# ECU_AutoRC_MOT_DRIVER_r00.net
KiCad netlist of a schematic drawn in Altium Designer
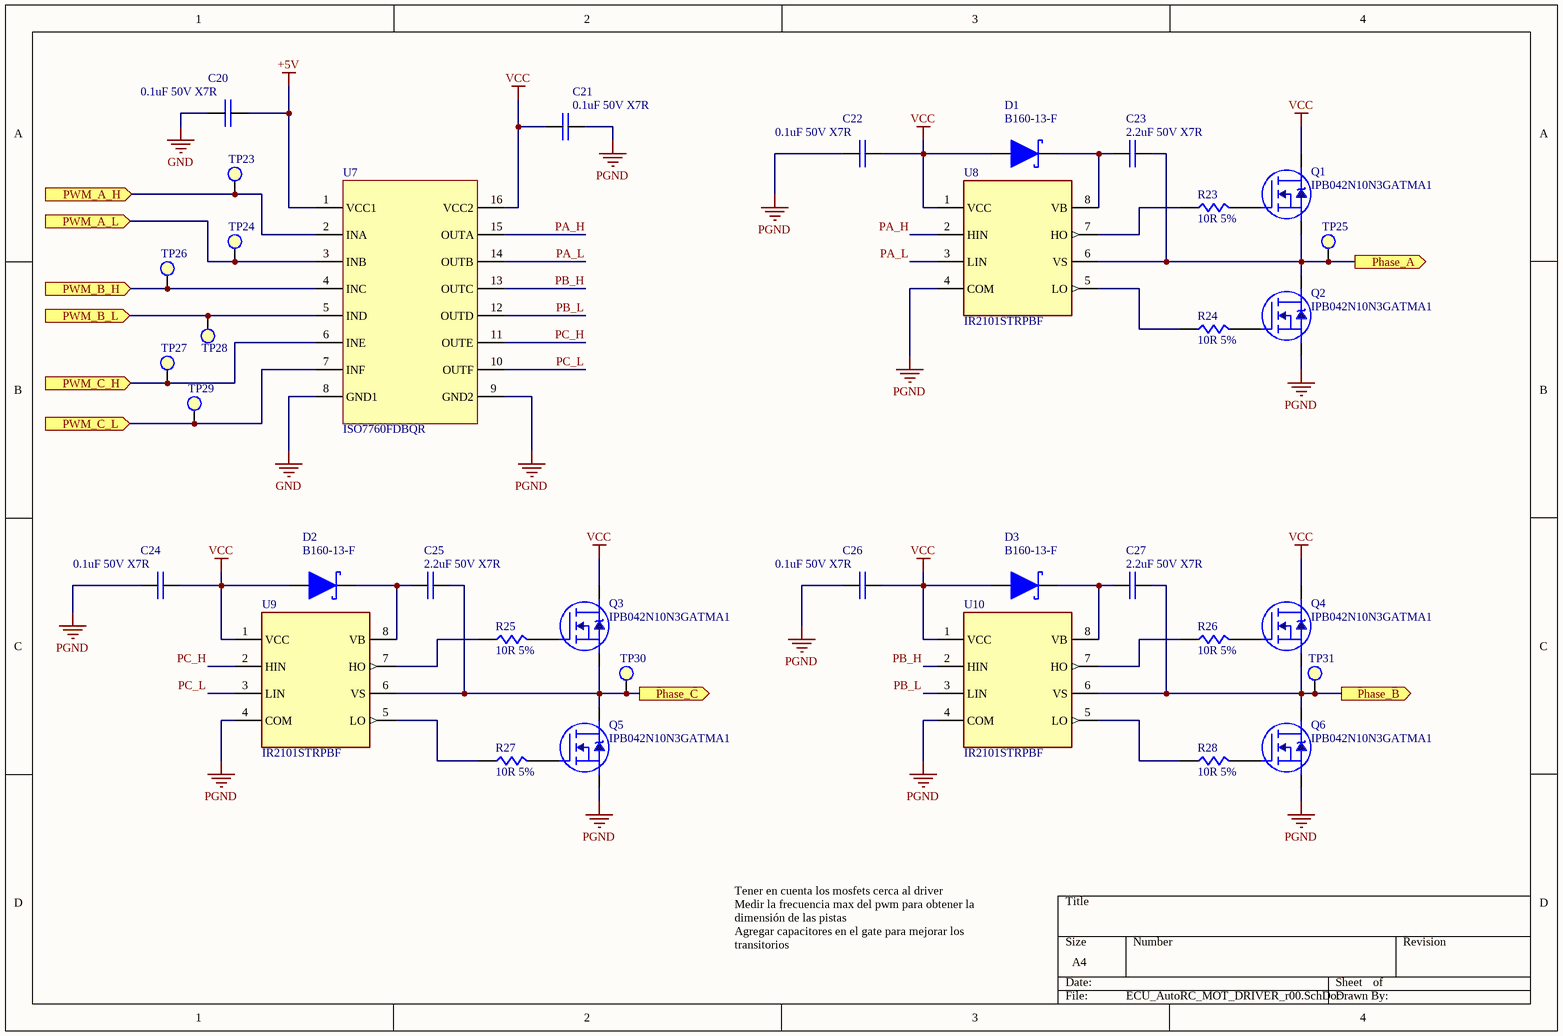
[diagram p0: ECU_AutoRC_MOT_DRIVER_r00.SchDoc]

(export (version "E")
  (design (tool "Eeschema 10.0.6"))
  (components
    (comp (ref "C20")
      (value "0.1uF 50V X7R")
      (footprint "C_0805")
      (description "Non Polarizated Capacitor")
      (libsource (lib "ECU_AutoRC_r00") (part "Capacitor NP"))
    )
    (comp (ref "C21")
      (value "0.1uF 50V X7R")
      (footprint "C_0805")
      (description "Non Polarizated Capacitor")
      (libsource (lib "ECU_AutoRC_r00") (part "Capacitor NP"))
    )
    (comp (ref "C22")
      (value "0.1uF 50V X7R")
      (footprint "C_0805")
      (description "Non Polarizated Capacitor")
      (libsource (lib "ECU_AutoRC_r00") (part "Capacitor NP"))
    )
    (comp (ref "C23")
      (value "2.2uF 50V X7R")
      (footprint "C_0805")
      (description "Non Polarizated Capacitor")
      (libsource (lib "ECU_AutoRC_r00") (part "Capacitor NP"))
    )
    (comp (ref "C24")
      (value "0.1uF 50V X7R")
      (footprint "C_0805")
      (description "Non Polarizated Capacitor")
      (libsource (lib "ECU_AutoRC_r00") (part "Capacitor NP"))
    )
    (comp (ref "C25")
      (value "2.2uF 50V X7R")
      (footprint "C_0805")
      (description "Non Polarizated Capacitor")
      (libsource (lib "ECU_AutoRC_r00") (part "Capacitor NP"))
    )
    (comp (ref "C26")
      (value "0.1uF 50V X7R")
      (footprint "C_0805")
      (description "Non Polarizated Capacitor")
      (libsource (lib "ECU_AutoRC_r00") (part "Capacitor NP"))
    )
    (comp (ref "C27")
      (value "2.2uF 50V X7R")
      (footprint "C_0805")
      (description "Non Polarizated Capacitor")
      (libsource (lib "ECU_AutoRC_r00") (part "Capacitor NP"))
    )
    (comp (ref "D1")
      (value "B160-13-F")
      (footprint "D_SMA")
      (description "Diode Schottky")
      (libsource (lib "ECU_AutoRC_r00") (part "Diode_Schottky"))
    )
    (comp (ref "D2")
      (value "B160-13-F")
      (footprint "D_SMA")
      (description "Diode Schottky")
      (libsource (lib "ECU_AutoRC_r00") (part "Diode_Schottky"))
    )
    (comp (ref "D3")
      (value "B160-13-F")
      (footprint "D_SMA")
      (description "Diode Schottky")
      (libsource (lib "ECU_AutoRC_r00") (part "Diode_Schottky"))
    )
    (comp (ref "Q1")
      (value "IPB042N10N3GATMA1")
      (footprint "TO263-3")
      (description "Mosfet N")
      (libsource (lib "ECU_AutoRC_r00") (part "NMOS"))
    )
    (comp (ref "Q2")
      (value "IPB042N10N3GATMA1")
      (footprint "TO263-3")
      (description "Mosfet N")
      (libsource (lib "ECU_AutoRC_r00") (part "NMOS"))
    )
    (comp (ref "Q3")
      (value "IPB042N10N3GATMA1")
      (footprint "TO263-3")
      (description "Mosfet N")
      (libsource (lib "ECU_AutoRC_r00") (part "NMOS"))
    )
    (comp (ref "Q4")
      (value "IPB042N10N3GATMA1")
      (footprint "TO263-3")
      (description "Mosfet N")
      (libsource (lib "ECU_AutoRC_r00") (part "NMOS"))
    )
    (comp (ref "Q5")
      (value "IPB042N10N3GATMA1")
      (footprint "TO263-3")
      (description "Mosfet N")
      (libsource (lib "ECU_AutoRC_r00") (part "NMOS"))
    )
    (comp (ref "Q6")
      (value "IPB042N10N3GATMA1")
      (footprint "TO263-3")
      (description "Mosfet N")
      (libsource (lib "ECU_AutoRC_r00") (part "NMOS"))
    )
    (comp (ref "R23")
      (value "10R 5%")
      (footprint "R_0805")
      (description "Resistor")
      (libsource (lib "ECU_AutoRC_r00") (part "Resistor"))
    )
    (comp (ref "R24")
      (value "10R 5%")
      (footprint "R_0805")
      (description "Resistor")
      (libsource (lib "ECU_AutoRC_r00") (part "Resistor"))
    )
    (comp (ref "R25")
      (value "10R 5%")
      (footprint "R_0805")
      (description "Resistor")
      (libsource (lib "ECU_AutoRC_r00") (part "Resistor"))
    )
    (comp (ref "R26")
      (value "10R 5%")
      (footprint "R_0805")
      (description "Resistor")
      (libsource (lib "ECU_AutoRC_r00") (part "Resistor"))
    )
    (comp (ref "R27")
      (value "10R 5%")
      (footprint "R_0805")
      (description "Resistor")
      (libsource (lib "ECU_AutoRC_r00") (part "Resistor"))
    )
    (comp (ref "R28")
      (value "10R 5%")
      (footprint "R_0805")
      (description "Resistor")
      (libsource (lib "ECU_AutoRC_r00") (part "Resistor"))
    )
    (comp (ref "TP23")
      (value "Test Point")
      (footprint "TEST_POINT")
      (libsource (lib "ECU_AutoRC_r00") (part "TestPoint"))
    )
    (comp (ref "TP24")
      (value "Test Point")
      (footprint "TEST_POINT")
      (libsource (lib "ECU_AutoRC_r00") (part "TestPoint"))
    )
    (comp (ref "TP25")
      (value "Test Point")
      (footprint "TEST_POINT")
      (libsource (lib "ECU_AutoRC_r00") (part "TestPoint"))
    )
    (comp (ref "TP26")
      (value "Test Point")
      (footprint "TEST_POINT")
      (libsource (lib "ECU_AutoRC_r00") (part "TestPoint"))
    )
    (comp (ref "TP27")
      (value "Test Point")
      (footprint "TEST_POINT")
      (libsource (lib "ECU_AutoRC_r00") (part "TestPoint"))
    )
    (comp (ref "TP28")
      (value "Test Point")
      (footprint "TEST_POINT")
      (libsource (lib "ECU_AutoRC_r00") (part "TestPoint"))
    )
    (comp (ref "TP29")
      (value "Test Point")
      (footprint "TEST_POINT")
      (libsource (lib "ECU_AutoRC_r00") (part "TestPoint"))
    )
    (comp (ref "TP30")
      (value "Test Point")
      (footprint "TEST_POINT")
      (libsource (lib "ECU_AutoRC_r00") (part "TestPoint"))
    )
    (comp (ref "TP31")
      (value "Test Point")
      (footprint "TEST_POINT")
      (libsource (lib "ECU_AutoRC_r00") (part "TestPoint"))
    )
    (comp (ref "U7")
      (value "ISO7760FDBQR")
      (footprint "IC_SSOP16")
      (description "DGTL ISOLTR 3KV 6CH GP 16-SSOP")
      (libsource (lib "ECU_AutoRC_r00") (part "ISO7760FDBQR"))
    )
    (comp (ref "U8")
      (value "IR2101STRPBF")
      (footprint "IC_8SOIC")
      (description "Half-Bridge Gate Driver IC Non-Inverting 8-SOIC")
      (libsource (lib "ECU_AutoRC_r00") (part "IR2101STRPBF"))
    )
    (comp (ref "U9")
      (value "IR2101STRPBF")
      (footprint "IC_8SOIC")
      (description "Half-Bridge Gate Driver IC Non-Inverting 8-SOIC")
      (libsource (lib "ECU_AutoRC_r00") (part "IR2101STRPBF"))
    )
    (comp (ref "U10")
      (value "IR2101STRPBF")
      (footprint "IC_8SOIC")
      (description "Half-Bridge Gate Driver IC Non-Inverting 8-SOIC")
      (libsource (lib "ECU_AutoRC_r00") (part "IR2101STRPBF"))
    )
  )
  (nets
    (net (code "1") (name "+5V") (class "Default")
      (node (ref "C20") (pin "2") (pinfunction "2_2") (pintype "passive"))
      (node (ref "U7") (pin "1") (pinfunction "VCC1_1") (pintype "passive"))
    )
    (net (code "2") (name "/PA_H") (class "Default")
      (node (ref "U7") (pin "15") (pinfunction "OUTA_15") (pintype "passive"))
      (node (ref "U8") (pin "2") (pinfunction "HIN_2") (pintype "passive"))
    )
    (net (code "3") (name "/PA_L") (class "Default")
      (node (ref "U7") (pin "14") (pinfunction "OUTB_14") (pintype "passive"))
      (node (ref "U8") (pin "3") (pinfunction "LIN_3") (pintype "passive"))
    )
    (net (code "4") (name "/PB_H") (class "Default")
      (node (ref "U10") (pin "2") (pinfunction "HIN_2") (pintype "passive"))
      (node (ref "U7") (pin "13") (pinfunction "OUTC_13") (pintype "passive"))
    )
    (net (code "5") (name "/PB_L") (class "Default")
      (node (ref "U10") (pin "3") (pinfunction "LIN_3") (pintype "passive"))
      (node (ref "U7") (pin "12") (pinfunction "OUTD_12") (pintype "passive"))
    )
    (net (code "6") (name "/PC_H") (class "Default")
      (node (ref "U7") (pin "11") (pinfunction "OUTE_11") (pintype "passive"))
      (node (ref "U9") (pin "2") (pinfunction "HIN_2") (pintype "passive"))
    )
    (net (code "7") (name "/PC_L") (class "Default")
      (node (ref "U7") (pin "10") (pinfunction "OUTF_10") (pintype "passive"))
      (node (ref "U9") (pin "3") (pinfunction "LIN_3") (pintype "passive"))
    )
    (net (code "8") (name "/PWM_A_H") (class "Default")
      (node (ref "TP23") (pin "1") (pintype "passive"))
      (node (ref "U7") (pin "2") (pinfunction "INA_2") (pintype "passive"))
    )
    (net (code "9") (name "/PWM_A_L") (class "Default")
      (node (ref "TP24") (pin "1") (pintype "passive"))
      (node (ref "U7") (pin "3") (pinfunction "INB_3") (pintype "passive"))
    )
    (net (code "10") (name "/PWM_B_H") (class "Default")
      (node (ref "TP26") (pin "1") (pintype "passive"))
      (node (ref "U7") (pin "4") (pinfunction "INC_4") (pintype "passive"))
    )
    (net (code "11") (name "/PWM_B_L") (class "Default")
      (node (ref "TP28") (pin "1") (pintype "passive"))
      (node (ref "U7") (pin "5") (pinfunction "IND_5") (pintype "passive"))
    )
    (net (code "12") (name "/PWM_C_H") (class "Default")
      (node (ref "TP27") (pin "1") (pintype "passive"))
      (node (ref "U7") (pin "6") (pinfunction "INE_6") (pintype "passive"))
    )
    (net (code "13") (name "/PWM_C_L") (class "Default")
      (node (ref "TP29") (pin "1") (pintype "passive"))
      (node (ref "U7") (pin "7") (pinfunction "INF_7") (pintype "passive"))
    )
    (net (code "14") (name "/Phase_A") (class "Default")
      (node (ref "C23") (pin "2") (pinfunction "2_2") (pintype "passive"))
      (node (ref "Q1") (pin "3") (pinfunction "SOURCE_3") (pintype "passive"))
      (node (ref "Q2") (pin "2") (pinfunction "DRAIN_2") (pintype "passive"))
      (node (ref "TP25") (pin "1") (pintype "passive"))
      (node (ref "U8") (pin "6") (pinfunction "VS_6") (pintype "passive"))
    )
    (net (code "15") (name "/Phase_B") (class "Default")
      (node (ref "C27") (pin "2") (pinfunction "2_2") (pintype "passive"))
      (node (ref "Q4") (pin "3") (pinfunction "SOURCE_3") (pintype "passive"))
      (node (ref "Q6") (pin "2") (pinfunction "DRAIN_2") (pintype "passive"))
      (node (ref "TP31") (pin "1") (pintype "passive"))
      (node (ref "U10") (pin "6") (pinfunction "VS_6") (pintype "passive"))
    )
    (net (code "16") (name "/Phase_C") (class "Default")
      (node (ref "C25") (pin "2") (pinfunction "2_2") (pintype "passive"))
      (node (ref "Q3") (pin "3") (pinfunction "SOURCE_3") (pintype "passive"))
      (node (ref "Q5") (pin "2") (pinfunction "DRAIN_2") (pintype "passive"))
      (node (ref "TP30") (pin "1") (pintype "passive"))
      (node (ref "U9") (pin "6") (pinfunction "VS_6") (pintype "passive"))
    )
    (net (code "17") (name "GND") (class "Default")
      (node (ref "C20") (pin "1") (pinfunction "1_1") (pintype "passive"))
      (node (ref "U7") (pin "8") (pinfunction "GND1_8") (pintype "passive"))
    )
    (net (code "18") (name "Net-(D1-Catode)") (class "Default")
      (node (ref "C23") (pin "1") (pinfunction "1_1") (pintype "passive"))
      (node (ref "D1") (pin "2") (pinfunction "Catode_2") (pintype "passive"))
      (node (ref "U8") (pin "8") (pinfunction "VB_8") (pintype "passive"))
    )
    (net (code "19") (name "Net-(D2-Catode)") (class "Default")
      (node (ref "C25") (pin "1") (pinfunction "1_1") (pintype "passive"))
      (node (ref "D2") (pin "2") (pinfunction "Catode_2") (pintype "passive"))
      (node (ref "U9") (pin "8") (pinfunction "VB_8") (pintype "passive"))
    )
    (net (code "20") (name "Net-(D3-Catode)") (class "Default")
      (node (ref "C27") (pin "1") (pinfunction "1_1") (pintype "passive"))
      (node (ref "D3") (pin "2") (pinfunction "Catode_2") (pintype "passive"))
      (node (ref "U10") (pin "8") (pinfunction "VB_8") (pintype "passive"))
    )
    (net (code "21") (name "Net-(Q1-GATE)") (class "Default")
      (node (ref "Q1") (pin "1") (pinfunction "GATE_1") (pintype "passive"))
      (node (ref "R23") (pin "2") (pinfunction "2_2") (pintype "passive"))
    )
    (net (code "22") (name "Net-(Q2-GATE)") (class "Default")
      (node (ref "Q2") (pin "1") (pinfunction "GATE_1") (pintype "passive"))
      (node (ref "R24") (pin "2") (pinfunction "2_2") (pintype "passive"))
    )
    (net (code "23") (name "Net-(Q3-GATE)") (class "Default")
      (node (ref "Q3") (pin "1") (pinfunction "GATE_1") (pintype "passive"))
      (node (ref "R25") (pin "2") (pinfunction "2_2") (pintype "passive"))
    )
    (net (code "24") (name "Net-(Q4-GATE)") (class "Default")
      (node (ref "Q4") (pin "1") (pinfunction "GATE_1") (pintype "passive"))
      (node (ref "R26") (pin "2") (pinfunction "2_2") (pintype "passive"))
    )
    (net (code "25") (name "Net-(Q5-GATE)") (class "Default")
      (node (ref "Q5") (pin "1") (pinfunction "GATE_1") (pintype "passive"))
      (node (ref "R27") (pin "2") (pinfunction "2_2") (pintype "passive"))
    )
    (net (code "26") (name "Net-(Q6-GATE)") (class "Default")
      (node (ref "Q6") (pin "1") (pinfunction "GATE_1") (pintype "passive"))
      (node (ref "R28") (pin "2") (pinfunction "2_2") (pintype "passive"))
    )
    (net (code "27") (name "Net-(U8-HO)") (class "Default")
      (node (ref "R23") (pin "1") (pinfunction "1_1") (pintype "passive"))
      (node (ref "U8") (pin "7") (pinfunction "HO_7") (pintype "output"))
    )
    (net (code "28") (name "Net-(U8-LO)") (class "Default")
      (node (ref "R24") (pin "1") (pinfunction "1_1") (pintype "passive"))
      (node (ref "U8") (pin "5") (pinfunction "LO_5") (pintype "output"))
    )
    (net (code "29") (name "Net-(U9-HO)") (class "Default")
      (node (ref "R25") (pin "1") (pinfunction "1_1") (pintype "passive"))
      (node (ref "U9") (pin "7") (pinfunction "HO_7") (pintype "output"))
    )
    (net (code "30") (name "Net-(U9-LO)") (class "Default")
      (node (ref "R27") (pin "1") (pinfunction "1_1") (pintype "passive"))
      (node (ref "U9") (pin "5") (pinfunction "LO_5") (pintype "output"))
    )
    (net (code "31") (name "Net-(U10-HO)") (class "Default")
      (node (ref "R26") (pin "1") (pinfunction "1_1") (pintype "passive"))
      (node (ref "U10") (pin "7") (pinfunction "HO_7") (pintype "output"))
    )
    (net (code "32") (name "Net-(U10-LO)") (class "Default")
      (node (ref "R28") (pin "1") (pinfunction "1_1") (pintype "passive"))
      (node (ref "U10") (pin "5") (pinfunction "LO_5") (pintype "output"))
    )
    (net (code "33") (name "PGND") (class "Default")
      (node (ref "C21") (pin "1") (pinfunction "1_1") (pintype "passive"))
      (node (ref "C22") (pin "1") (pinfunction "1_1") (pintype "passive"))
      (node (ref "C24") (pin "1") (pinfunction "1_1") (pintype "passive"))
      (node (ref "C26") (pin "1") (pinfunction "1_1") (pintype "passive"))
      (node (ref "Q2") (pin "3") (pinfunction "SOURCE_3") (pintype "passive"))
      (node (ref "Q5") (pin "3") (pinfunction "SOURCE_3") (pintype "passive"))
      (node (ref "Q6") (pin "3") (pinfunction "SOURCE_3") (pintype "passive"))
      (node (ref "U10") (pin "4") (pinfunction "COM_4") (pintype "passive"))
      (node (ref "U7") (pin "9") (pinfunction "GND2_9") (pintype "passive"))
      (node (ref "U8") (pin "4") (pinfunction "COM_4") (pintype "passive"))
      (node (ref "U9") (pin "4") (pinfunction "COM_4") (pintype "passive"))
    )
    (net (code "34") (name "VCC") (class "Default")
      (node (ref "C21") (pin "2") (pinfunction "2_2") (pintype "passive"))
      (node (ref "C22") (pin "2") (pinfunction "2_2") (pintype "passive"))
      (node (ref "C24") (pin "2") (pinfunction "2_2") (pintype "passive"))
      (node (ref "C26") (pin "2") (pinfunction "2_2") (pintype "passive"))
      (node (ref "D1") (pin "1") (pinfunction "Anode_1") (pintype "passive"))
      (node (ref "D2") (pin "1") (pinfunction "Anode_1") (pintype "passive"))
      (node (ref "D3") (pin "1") (pinfunction "Anode_1") (pintype "passive"))
      (node (ref "Q1") (pin "2") (pinfunction "DRAIN_2") (pintype "passive"))
      (node (ref "Q3") (pin "2") (pinfunction "DRAIN_2") (pintype "passive"))
      (node (ref "Q4") (pin "2") (pinfunction "DRAIN_2") (pintype "passive"))
      (node (ref "U10") (pin "1") (pinfunction "VCC_1") (pintype "passive"))
      (node (ref "U7") (pin "16") (pinfunction "VCC2_16") (pintype "passive"))
      (node (ref "U8") (pin "1") (pinfunction "VCC_1") (pintype "passive"))
      (node (ref "U9") (pin "1") (pinfunction "VCC_1") (pintype "passive"))
    )
  )
)
